# Radio_Module.net
KiCad netlist of a schematic drawn in Altium Designer
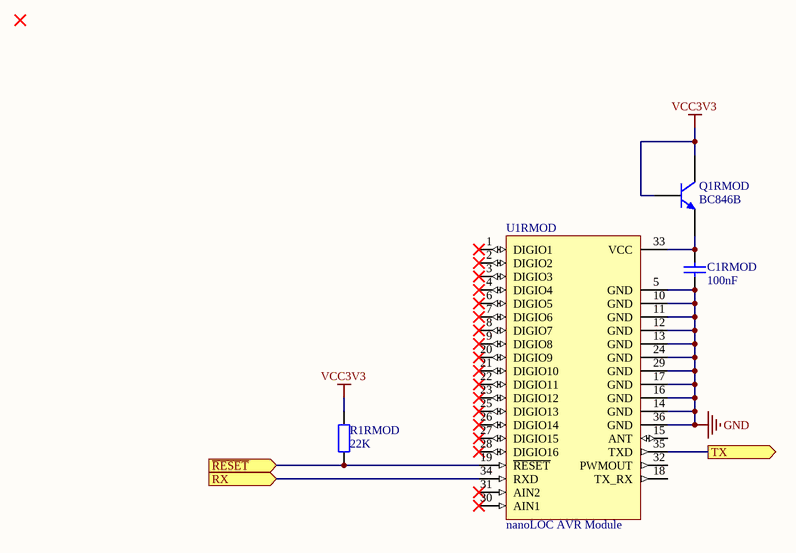
[diagram p0: Radio_Module.SchDoc]

(export (version "E")
  (design (tool "Eeschema 10.0.6"))
  (components
    (comp (ref "C1RMOD")
      (value "100nF")
      (footprint "CC1608-0603")
      (description "Capacitor")
      (fields (field (name "Comment") "Cap"))
      (libsource (lib "*") (part "Cap"))
    )
    (comp (ref "Q1RMOD")
      (value "BC846B")
      (footprint "SO-G3")
      (description "NPN Bipolar Transistor")
      (fields (field (name "MANUFACTURER") "NXP"))
      (libsource (lib "Comp") (part "BC846B"))
    )
    (comp (ref "R1RMOD")
      (value "22K")
      (footprint "CR1608-0603")
      (description "Resistor")
      (fields (field (name "Comment") "Res"))
      (libsource (lib "Comp") (part "Res"))
    )
    (comp (ref "U1RMOD")
      (value "nanoLOC AVR Module")
      (footprint "nano_LOC_AVR_Module35x14")
      (description "Radio Transceiver and Localisation module")
      (fields (field (name "MANUFACTURER") "NanoTron Inc."))
      (libsource (lib "Comp") (part "nanoLOC AVR Module"))
    )
  )
  (nets
    (net (code "1") (name "/RX") (class "Default")
      (node (ref "U1RMOD") (pin "34") (pinfunction "RXD_34") (pintype "input"))
    )
    (net (code "2") (name "/TX") (class "Default")
      (node (ref "U1RMOD") (pin "35") (pinfunction "TXD_35") (pintype "output"))
    )
    (net (code "3") (name "/~{RESET}") (class "Default")
      (node (ref "R1RMOD") (pin "1") (pinfunction "1_1") (pintype "passive"))
      (node (ref "U1RMOD") (pin "19") (pinfunction "~{RESET}_19") (pintype "input"))
    )
    (net (code "4") (name "GND") (class "Default")
      (node (ref "C1RMOD") (pin "1") (pinfunction "1_1") (pintype "passive"))
      (node (ref "U1RMOD") (pin "10") (pinfunction "GND_10") (pintype "power_in"))
      (node (ref "U1RMOD") (pin "11") (pinfunction "GND_11") (pintype "power_in"))
      (node (ref "U1RMOD") (pin "12") (pinfunction "GND_12") (pintype "power_in"))
      (node (ref "U1RMOD") (pin "13") (pinfunction "GND_13") (pintype "power_in"))
      (node (ref "U1RMOD") (pin "14") (pinfunction "GND_14") (pintype "power_in"))
      (node (ref "U1RMOD") (pin "16") (pinfunction "GND_16") (pintype "power_in"))
      (node (ref "U1RMOD") (pin "17") (pinfunction "GND_17") (pintype "power_in"))
      (node (ref "U1RMOD") (pin "24") (pinfunction "GND_24") (pintype "power_in"))
      (node (ref "U1RMOD") (pin "29") (pinfunction "GND_29") (pintype "power_in"))
      (node (ref "U1RMOD") (pin "36") (pinfunction "GND_36") (pintype "power_in"))
      (node (ref "U1RMOD") (pin "5") (pinfunction "GND_5") (pintype "power_in"))
    )
    (net (code "5") (name "Net-(Q1RMOD-E)") (class "Default")
      (node (ref "C1RMOD") (pin "2") (pinfunction "2_2") (pintype "passive"))
      (node (ref "Q1RMOD") (pin "2") (pinfunction "E_2") (pintype "passive"))
      (node (ref "U1RMOD") (pin "33") (pinfunction "VCC_33") (pintype "power_in"))
    )
    (net (code "6") (name "VCC3V3") (class "Default")
      (node (ref "Q1RMOD") (pin "1") (pinfunction "B_1") (pintype "passive"))
      (node (ref "Q1RMOD") (pin "3") (pinfunction "C_3") (pintype "passive"))
      (node (ref "R1RMOD") (pin "2") (pinfunction "2_2") (pintype "passive"))
    )
    (net (code "7") (name "unconnected-(U1RMOD-AIN1-Pad30)") (class "Default")
      (node (ref "U1RMOD") (pin "30") (pinfunction "AIN1_30") (pintype "input+no_connect"))
    )
    (net (code "8") (name "unconnected-(U1RMOD-AIN2-Pad31)") (class "Default")
      (node (ref "U1RMOD") (pin "31") (pinfunction "AIN2_31") (pintype "input+no_connect"))
    )
    (net (code "9") (name "unconnected-(U1RMOD-ANT-Pad15)") (class "Default")
      (node (ref "U1RMOD") (pin "15") (pinfunction "ANT_15") (pintype "bidirectional"))
    )
    (net (code "10") (name "unconnected-(U1RMOD-DIGIO1-Pad1)") (class "Default")
      (node (ref "U1RMOD") (pin "1") (pinfunction "DIGIO1_1") (pintype "bidirectional+no_connect"))
    )
    (net (code "11") (name "unconnected-(U1RMOD-DIGIO2-Pad2)") (class "Default")
      (node (ref "U1RMOD") (pin "2") (pinfunction "DIGIO2_2") (pintype "bidirectional+no_connect"))
    )
    (net (code "12") (name "unconnected-(U1RMOD-DIGIO3-Pad3)") (class "Default")
      (node (ref "U1RMOD") (pin "3") (pinfunction "DIGIO3_3") (pintype "bidirectional+no_connect"))
    )
    (net (code "13") (name "unconnected-(U1RMOD-DIGIO4-Pad4)") (class "Default")
      (node (ref "U1RMOD") (pin "4") (pinfunction "DIGIO4_4") (pintype "bidirectional+no_connect"))
    )
    (net (code "14") (name "unconnected-(U1RMOD-DIGIO5-Pad6)") (class "Default")
      (node (ref "U1RMOD") (pin "6") (pinfunction "DIGIO5_6") (pintype "bidirectional+no_connect"))
    )
    (net (code "15") (name "unconnected-(U1RMOD-DIGIO6-Pad7)") (class "Default")
      (node (ref "U1RMOD") (pin "7") (pinfunction "DIGIO6_7") (pintype "bidirectional+no_connect"))
    )
    (net (code "16") (name "unconnected-(U1RMOD-DIGIO7-Pad8)") (class "Default")
      (node (ref "U1RMOD") (pin "8") (pinfunction "DIGIO7_8") (pintype "bidirectional+no_connect"))
    )
    (net (code "17") (name "unconnected-(U1RMOD-DIGIO8-Pad9)") (class "Default")
      (node (ref "U1RMOD") (pin "9") (pinfunction "DIGIO8_9") (pintype "bidirectional+no_connect"))
    )
    (net (code "18") (name "unconnected-(U1RMOD-DIGIO9-Pad20)") (class "Default")
      (node (ref "U1RMOD") (pin "20") (pinfunction "DIGIO9_20") (pintype "bidirectional+no_connect"))
    )
    (net (code "19") (name "unconnected-(U1RMOD-DIGIO10-Pad21)") (class "Default")
      (node (ref "U1RMOD") (pin "21") (pinfunction "DIGIO10_21") (pintype "bidirectional+no_connect"))
    )
    (net (code "20") (name "unconnected-(U1RMOD-DIGIO11-Pad22)") (class "Default")
      (node (ref "U1RMOD") (pin "22") (pinfunction "DIGIO11_22") (pintype "bidirectional+no_connect"))
    )
    (net (code "21") (name "unconnected-(U1RMOD-DIGIO12-Pad23)") (class "Default")
      (node (ref "U1RMOD") (pin "23") (pinfunction "DIGIO12_23") (pintype "bidirectional+no_connect"))
    )
    (net (code "22") (name "unconnected-(U1RMOD-DIGIO13-Pad25)") (class "Default")
      (node (ref "U1RMOD") (pin "25") (pinfunction "DIGIO13_25") (pintype "bidirectional+no_connect"))
    )
    (net (code "23") (name "unconnected-(U1RMOD-DIGIO14-Pad26)") (class "Default")
      (node (ref "U1RMOD") (pin "26") (pinfunction "DIGIO14_26") (pintype "bidirectional+no_connect"))
    )
    (net (code "24") (name "unconnected-(U1RMOD-DIGIO15-Pad27)") (class "Default")
      (node (ref "U1RMOD") (pin "27") (pinfunction "DIGIO15_27") (pintype "bidirectional+no_connect"))
    )
    (net (code "25") (name "unconnected-(U1RMOD-DIGIO16-Pad28)") (class "Default")
      (node (ref "U1RMOD") (pin "28") (pinfunction "DIGIO16_28") (pintype "bidirectional+no_connect"))
    )
    (net (code "26") (name "unconnected-(U1RMOD-PWMOUT-Pad32)") (class "Default")
      (node (ref "U1RMOD") (pin "32") (pinfunction "PWMOUT_32") (pintype "output"))
    )
    (net (code "27") (name "unconnected-(U1RMOD-TX_RX-Pad18)") (class "Default")
      (node (ref "U1RMOD") (pin "18") (pinfunction "TX_RX_18") (pintype "output"))
    )
  )
)
